# bristol_longshot.net
KiCad netlist of a schematic drawn in EAGLE
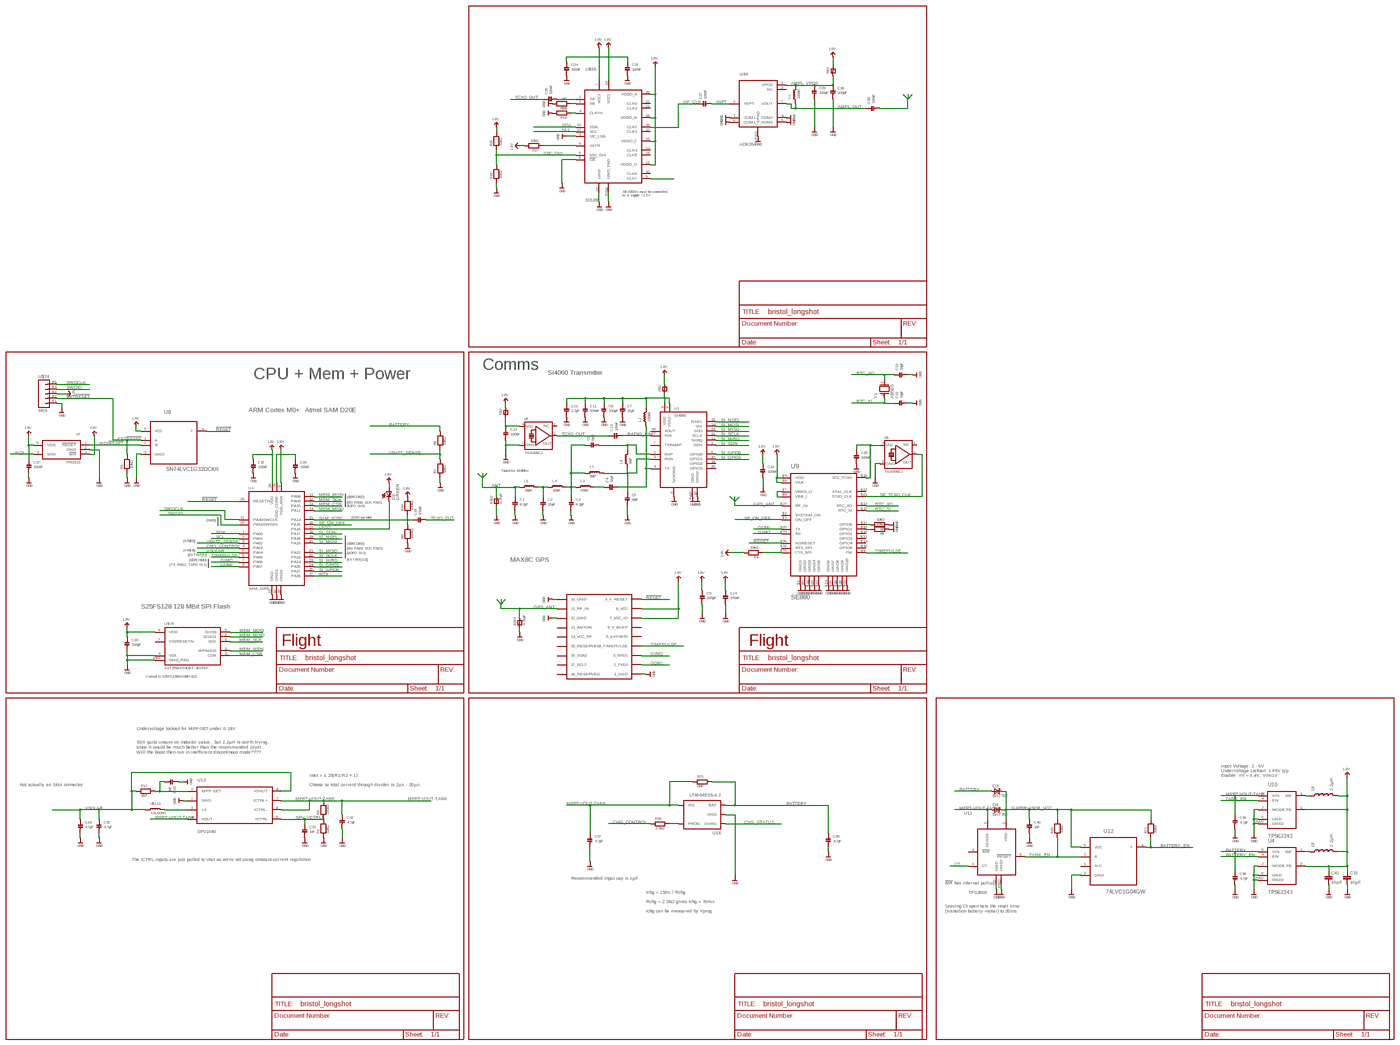
[diagram p0: schematic, sheet 1, overview]
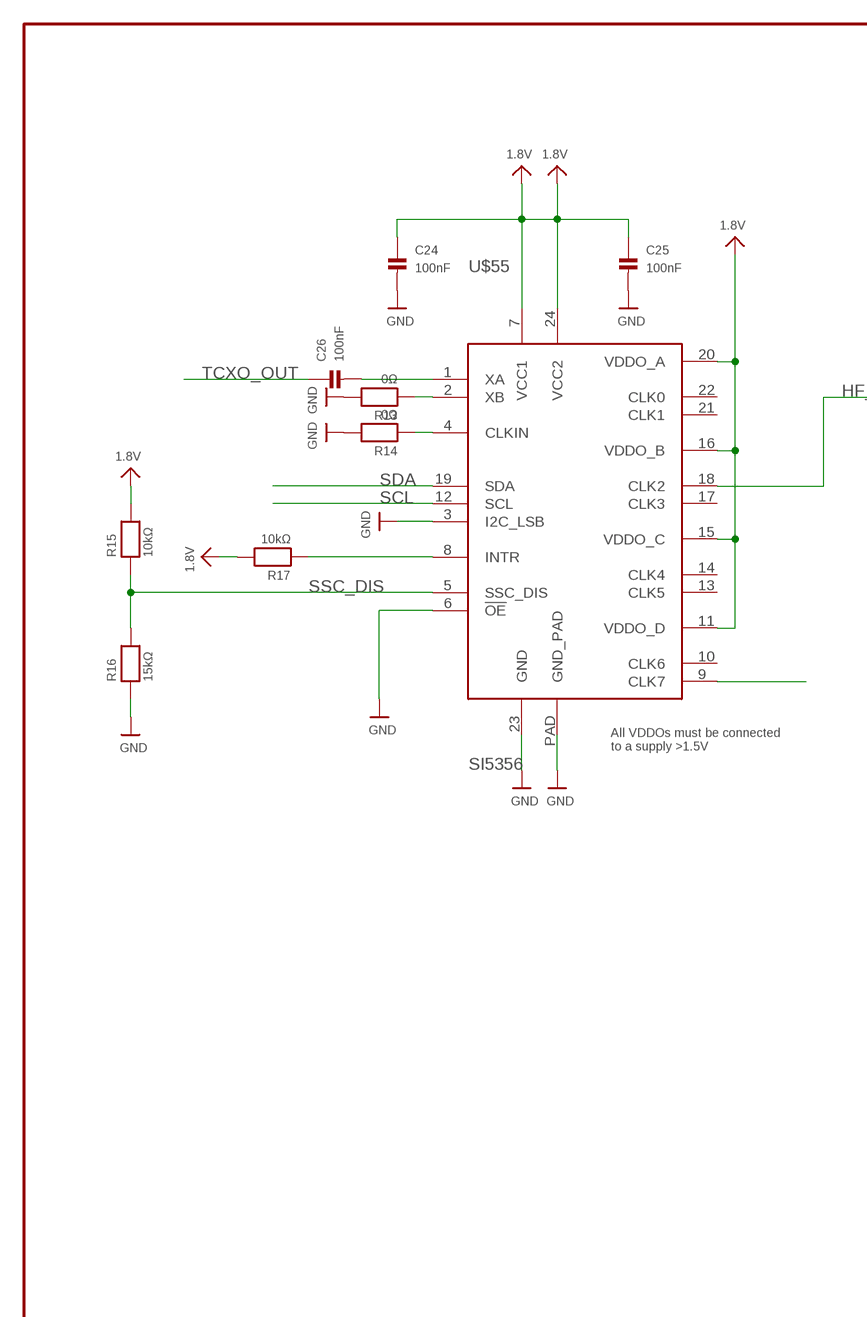
[diagram p1: schematic, sheet 1, part 1 of 4]
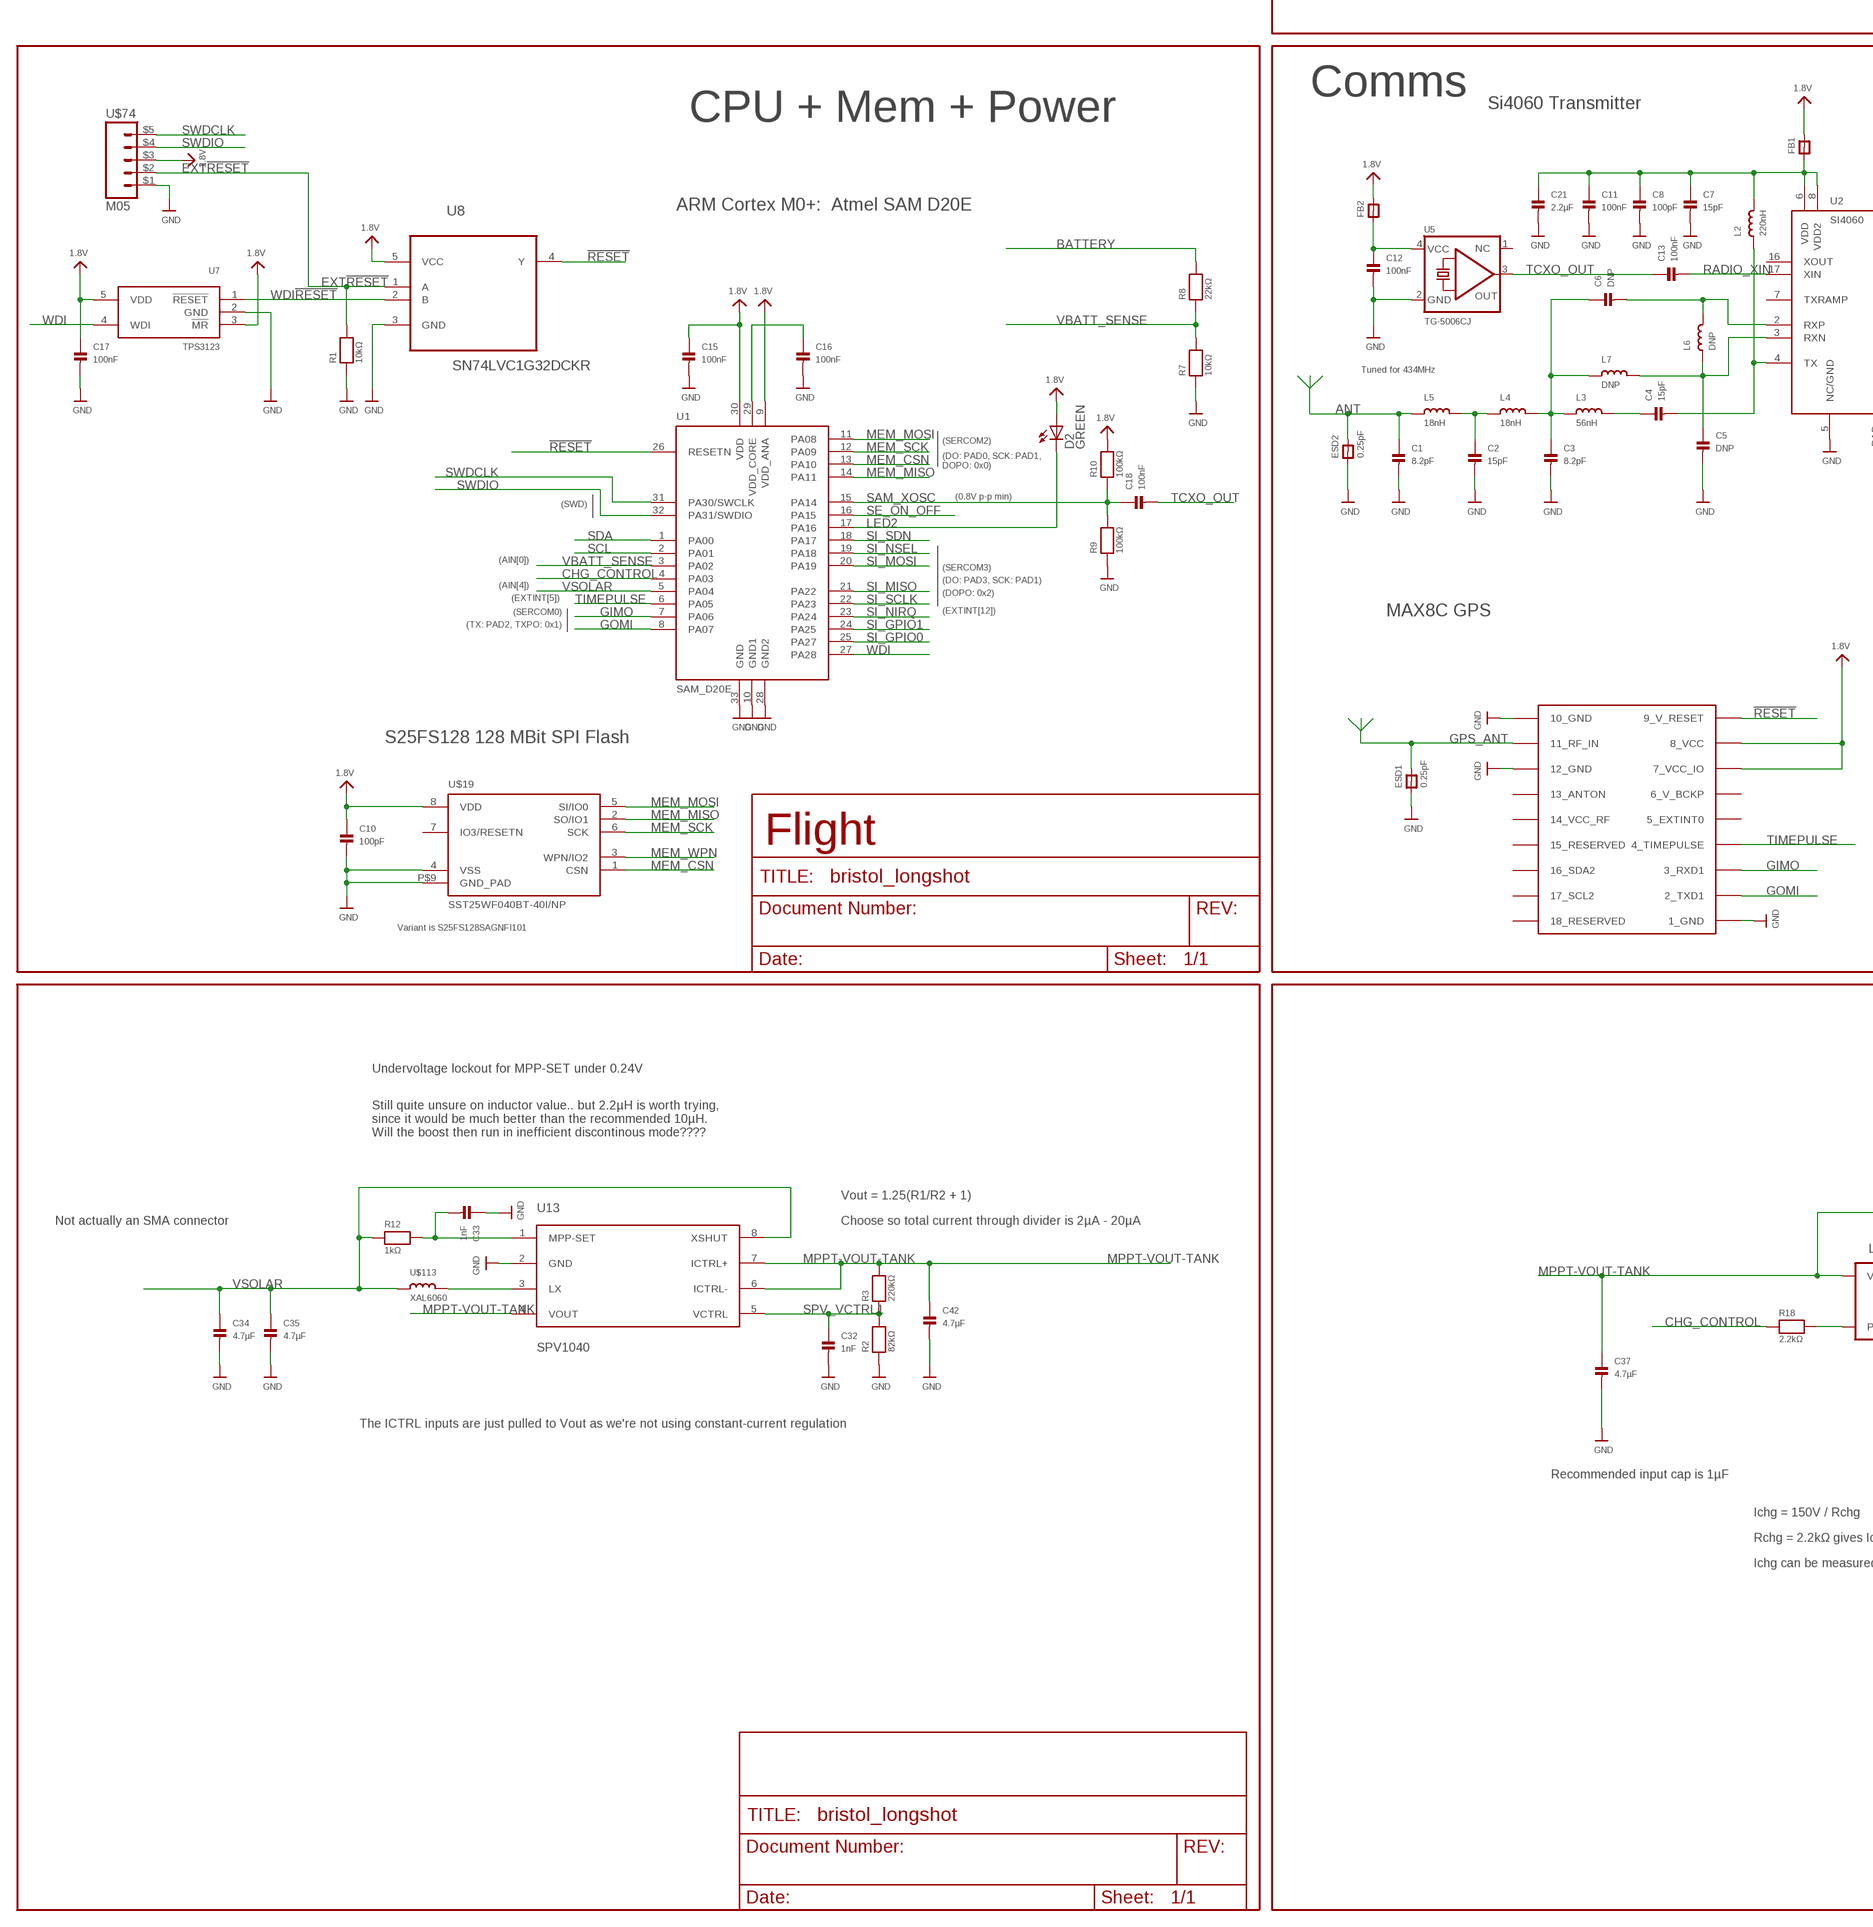
[diagram p2: schematic, sheet 1, part 2 of 4]
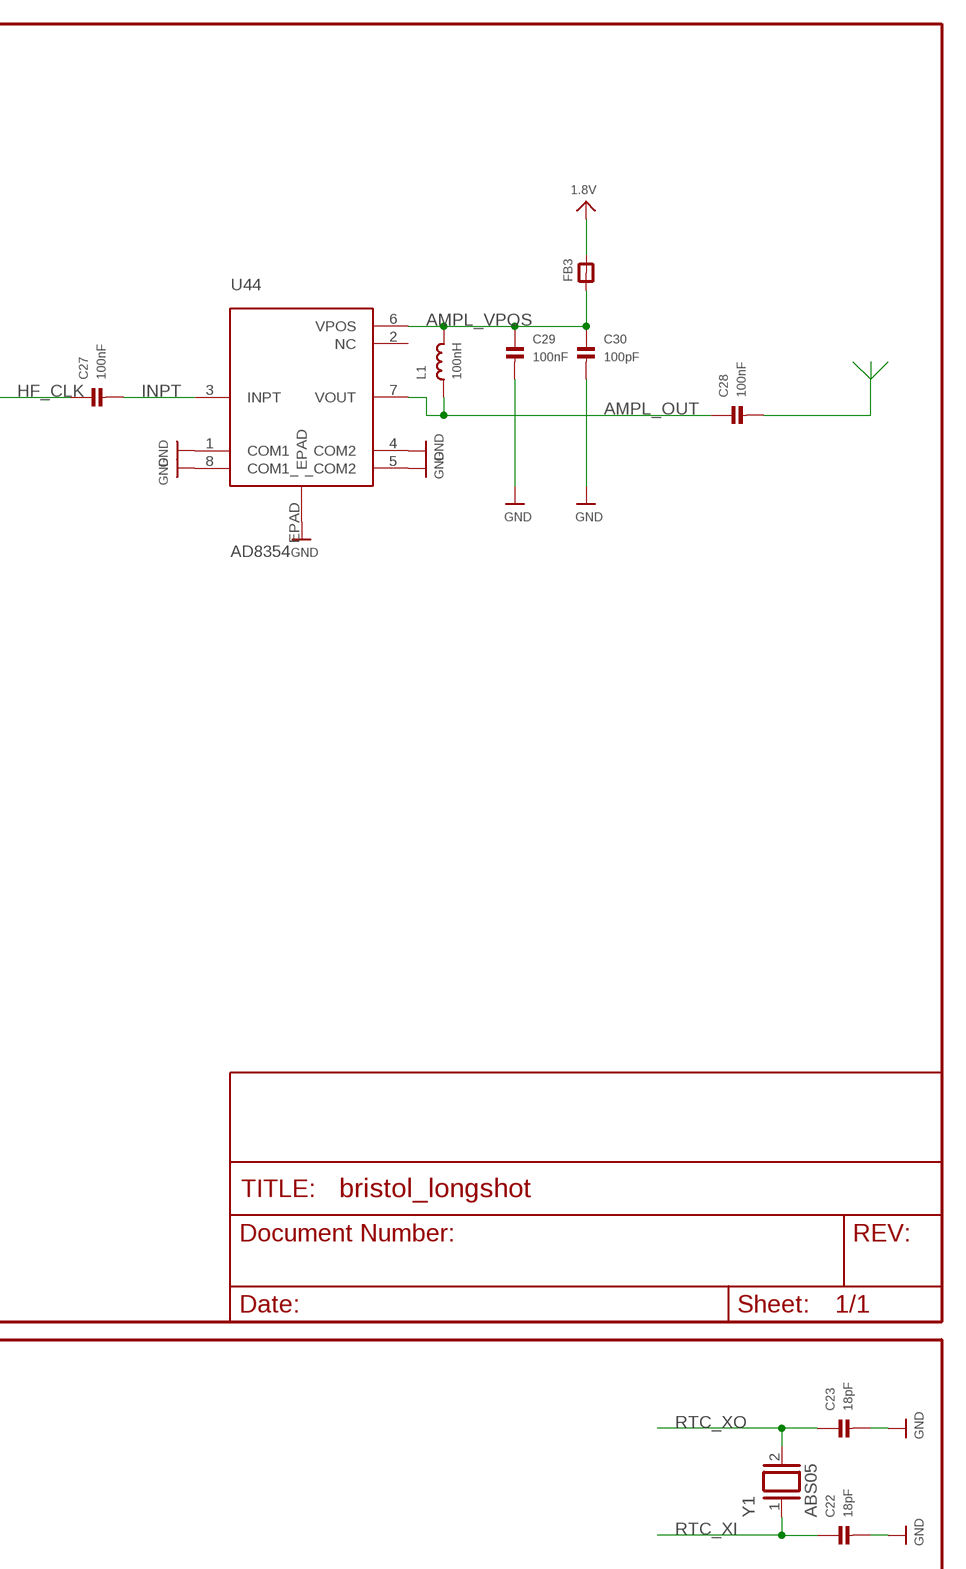
[diagram p3: schematic, sheet 1, part 3 of 4]
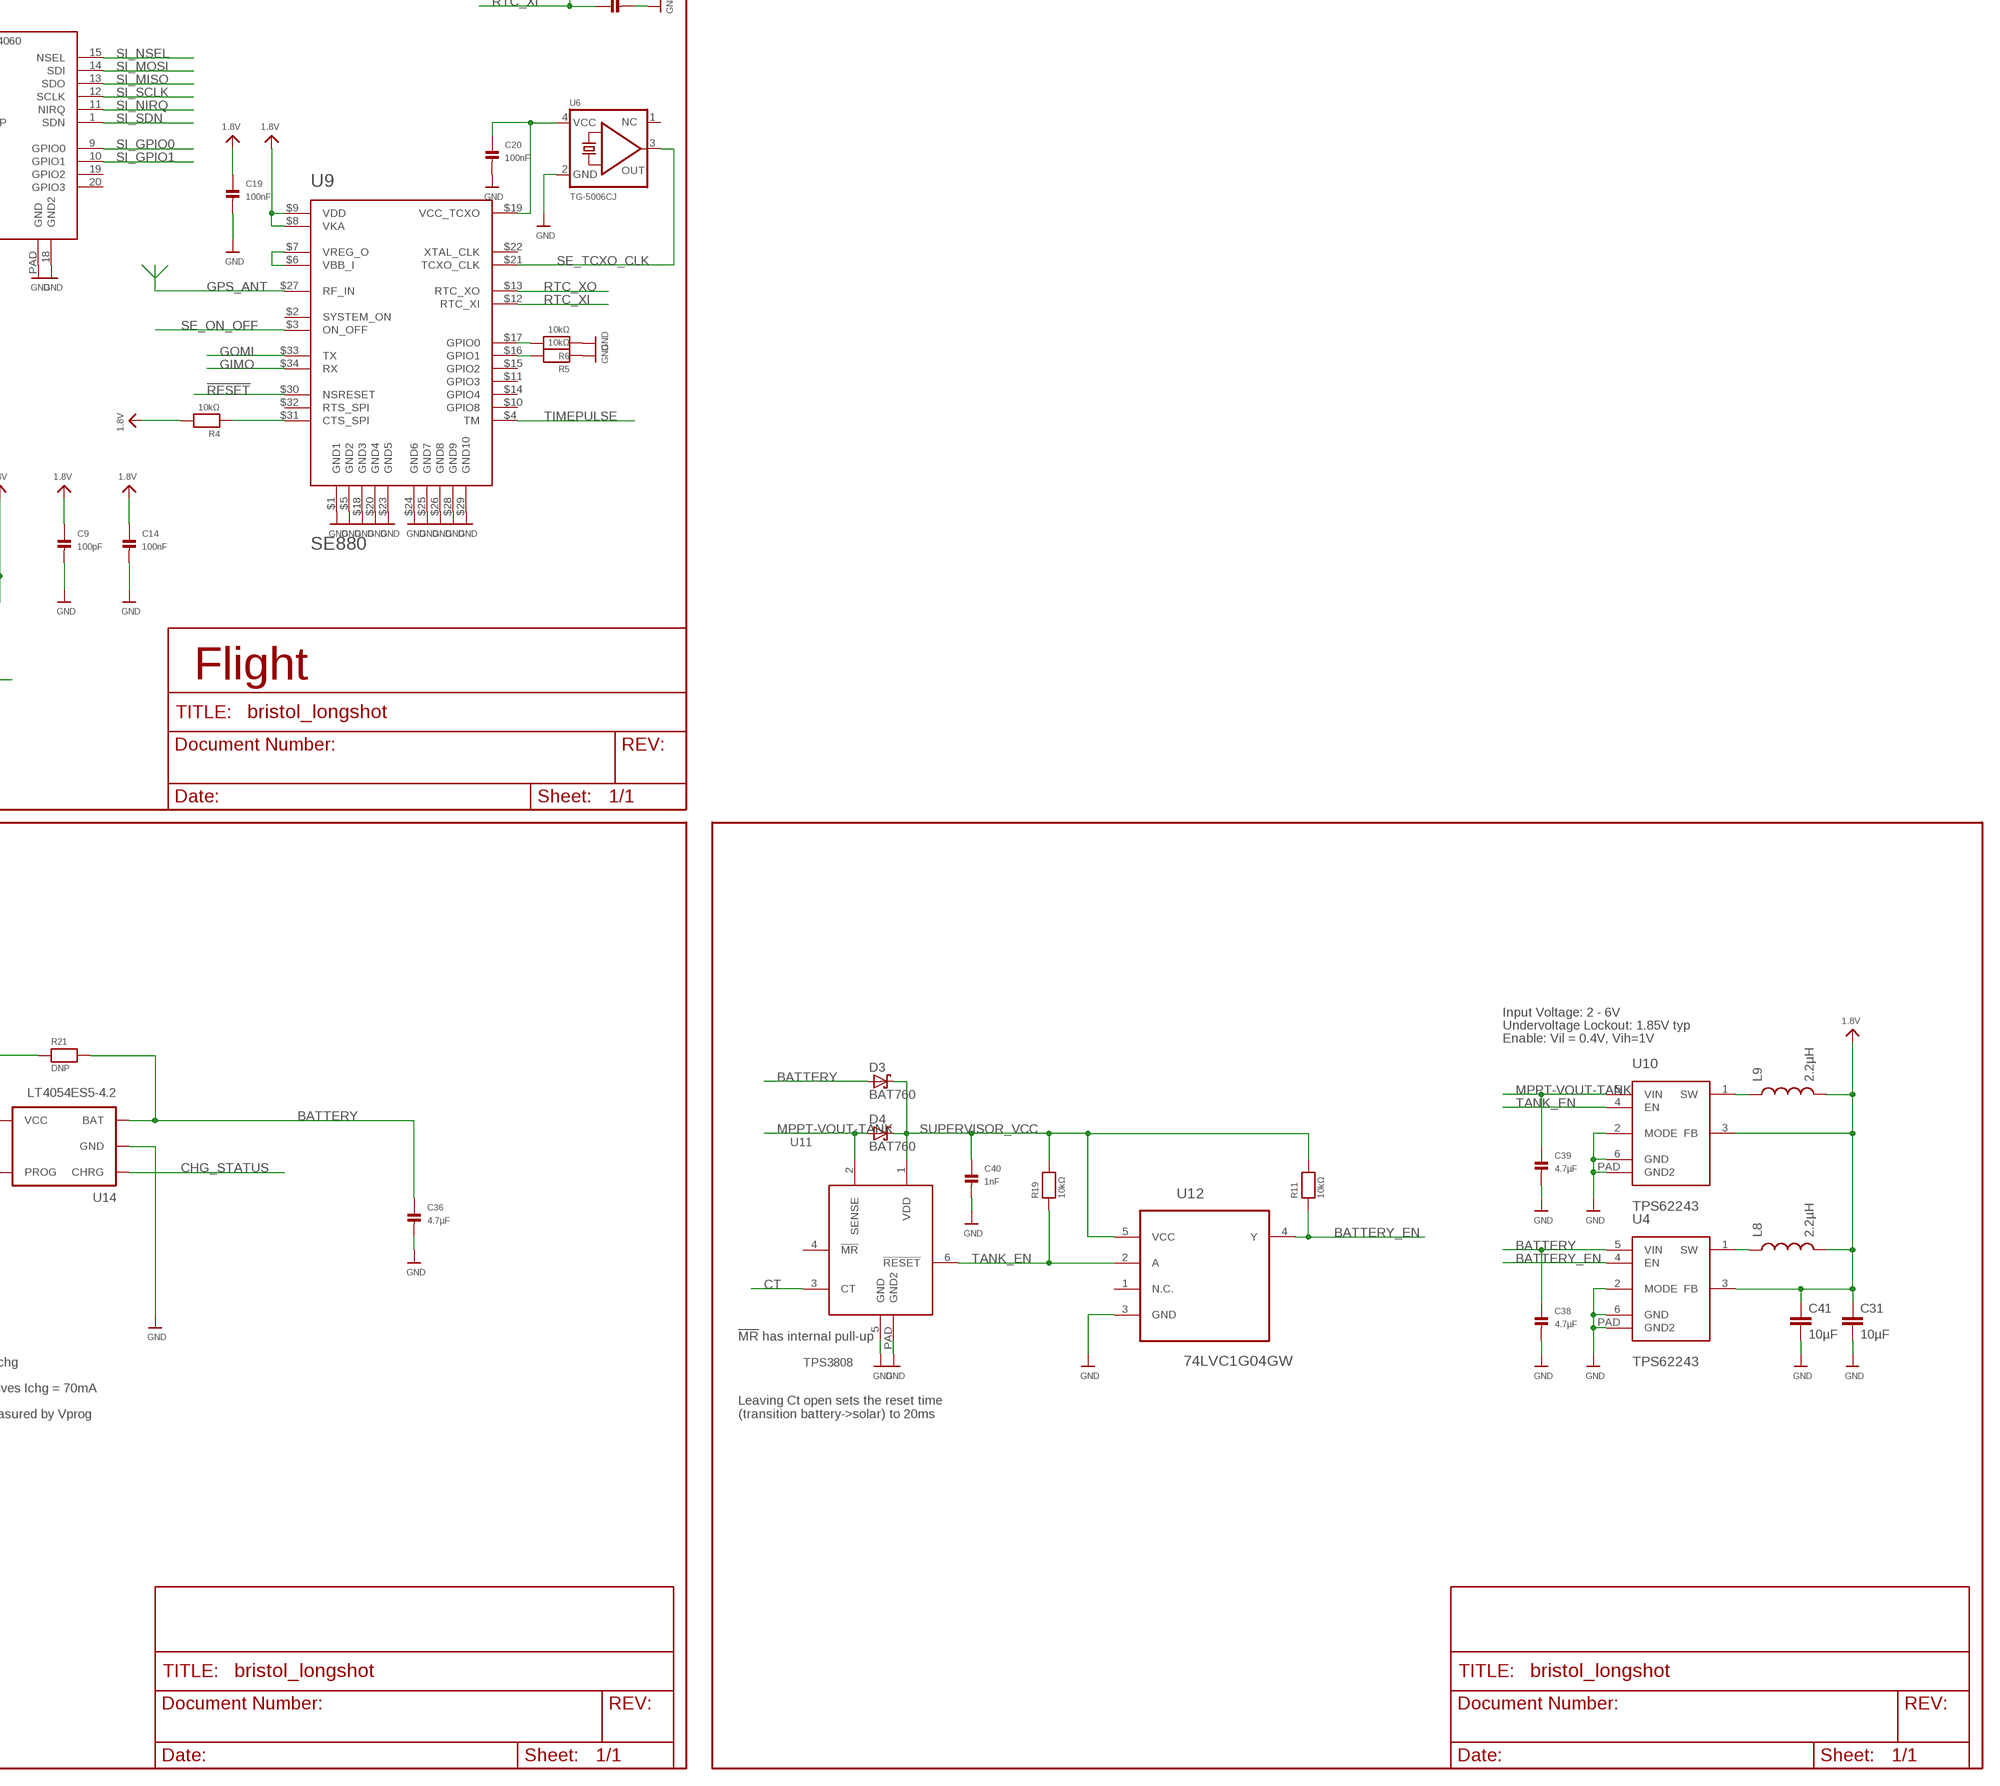
[diagram p4: schematic, sheet 1, part 4 of 4]

(export (version "E")
  (design (tool "Eeschema 10.0.6"))
  (components
    (comp (ref "C1")
      (value "8.2pF")
      (footprint "eagle-import:_0402")
      (libsource (lib "eagle-import") (part "CAP_CERAMIC_0402"))
    )
    (comp (ref "C2")
      (value "15pF")
      (footprint "eagle-import:_0402")
      (libsource (lib "eagle-import") (part "CAP_CERAMIC_0402"))
    )
    (comp (ref "C3")
      (value "8.2pF")
      (footprint "eagle-import:_0402")
      (libsource (lib "eagle-import") (part "CAP_CERAMIC_0402"))
    )
    (comp (ref "C4")
      (value "15pF")
      (footprint "eagle-import:_0402")
      (libsource (lib "eagle-import") (part "CAP_CERAMIC_0402"))
    )
    (comp (ref "C5")
      (value "DNP")
      (footprint "eagle-import:_0402")
      (libsource (lib "eagle-import") (part "CAP_CERAMIC_0402"))
    )
    (comp (ref "C6")
      (value "DNP")
      (footprint "eagle-import:_0402")
      (libsource (lib "eagle-import") (part "CAP_CERAMIC_0402"))
    )
    (comp (ref "C7")
      (value "15pF")
      (footprint "eagle-import:_0402")
      (libsource (lib "eagle-import") (part "CAP_CERAMIC_0402"))
    )
    (comp (ref "C8")
      (value "100pF")
      (footprint "eagle-import:_0402")
      (libsource (lib "eagle-import") (part "CAP_CERAMIC_0402"))
    )
    (comp (ref "C9")
      (value "100pF")
      (footprint "eagle-import:_0402")
      (libsource (lib "eagle-import") (part "CAP_CERAMIC_0402"))
    )
    (comp (ref "C10")
      (value "100pF")
      (footprint "eagle-import:_0402")
      (libsource (lib "eagle-import") (part "CAP_CERAMIC_0402"))
    )
    (comp (ref "C11")
      (value "100nF")
      (footprint "eagle-import:_0402")
      (libsource (lib "eagle-import") (part "CAP_CERAMIC_0402"))
    )
    (comp (ref "C12")
      (value "100nF")
      (footprint "eagle-import:_0402")
      (libsource (lib "eagle-import") (part "CAP_CERAMIC_0402"))
    )
    (comp (ref "C13")
      (value "100nF")
      (footprint "eagle-import:_0402")
      (libsource (lib "eagle-import") (part "CAP_CERAMIC_0402"))
    )
    (comp (ref "C14")
      (value "100nF")
      (footprint "eagle-import:_0402")
      (libsource (lib "eagle-import") (part "CAP_CERAMIC_0402"))
    )
    (comp (ref "C15")
      (value "100nF")
      (footprint "eagle-import:_0402")
      (libsource (lib "eagle-import") (part "CAP_CERAMIC_0402"))
    )
    (comp (ref "C16")
      (value "100nF")
      (footprint "eagle-import:_0402")
      (libsource (lib "eagle-import") (part "CAP_CERAMIC_0402"))
    )
    (comp (ref "C17")
      (value "100nF")
      (footprint "eagle-import:_0402")
      (libsource (lib "eagle-import") (part "CAP_CERAMIC_0402"))
    )
    (comp (ref "C18")
      (value "100nF")
      (footprint "eagle-import:_0402")
      (libsource (lib "eagle-import") (part "CAP_CERAMIC_0402"))
    )
    (comp (ref "C19")
      (value "100nF")
      (footprint "eagle-import:_0402")
      (libsource (lib "eagle-import") (part "CAP_CERAMIC_0402"))
    )
    (comp (ref "C20")
      (value "100nF")
      (footprint "eagle-import:_0402")
      (libsource (lib "eagle-import") (part "CAP_CERAMIC_0402"))
    )
    (comp (ref "C21")
      (value "2.2µF")
      (footprint "eagle-import:_0402")
      (libsource (lib "eagle-import") (part "CAP_CERAMIC_0402"))
    )
    (comp (ref "C22")
      (value "18pF")
      (footprint "eagle-import:_0402")
      (libsource (lib "eagle-import") (part "CAP_CERAMIC_0402"))
    )
    (comp (ref "C23")
      (value "18pF")
      (footprint "eagle-import:_0402")
      (libsource (lib "eagle-import") (part "CAP_CERAMIC_0402"))
    )
    (comp (ref "C24")
      (value "100nF")
      (footprint "eagle-import:_0402")
      (libsource (lib "eagle-import") (part "CAP_CERAMIC_0402"))
    )
    (comp (ref "C25")
      (value "100nF")
      (footprint "eagle-import:_0402")
      (libsource (lib "eagle-import") (part "CAP_CERAMIC_0402"))
    )
    (comp (ref "C26")
      (value "100nF")
      (footprint "eagle-import:_0402")
      (libsource (lib "eagle-import") (part "CAP_CERAMIC_0402"))
    )
    (comp (ref "C27")
      (value "100nF")
      (footprint "eagle-import:_0402")
      (libsource (lib "eagle-import") (part "CAP_CERAMIC_0402"))
    )
    (comp (ref "C28")
      (value "100nF")
      (footprint "eagle-import:_0402")
      (libsource (lib "eagle-import") (part "CAP_CERAMIC_0402"))
    )
    (comp (ref "C29")
      (value "100nF")
      (footprint "eagle-import:_0402")
      (libsource (lib "eagle-import") (part "CAP_CERAMIC_0402"))
    )
    (comp (ref "C30")
      (value "100pF")
      (footprint "eagle-import:_0402")
      (libsource (lib "eagle-import") (part "CAP_CERAMIC_0402"))
    )
    (comp (ref "C31")
      (value "10µF")
      (footprint "eagle-import:C0603K")
      (libsource (lib "eagle-import") (part "C-EUC0603K"))
    )
    (comp (ref "C32")
      (value "1nF")
      (footprint "eagle-import:_0402")
      (libsource (lib "eagle-import") (part "CAP_CERAMIC_0402"))
    )
    (comp (ref "C33")
      (value "1nF")
      (footprint "eagle-import:_0402")
      (libsource (lib "eagle-import") (part "CAP_CERAMIC_0402"))
    )
    (comp (ref "C34")
      (value "4.7µF")
      (footprint "eagle-import:_0402")
      (libsource (lib "eagle-import") (part "CAP_CERAMIC_0402"))
    )
    (comp (ref "C35")
      (value "4.7µF")
      (footprint "eagle-import:_0402")
      (libsource (lib "eagle-import") (part "CAP_CERAMIC_0402"))
    )
    (comp (ref "C36")
      (value "4.7µF")
      (footprint "eagle-import:_0402")
      (libsource (lib "eagle-import") (part "CAP_CERAMIC_0402"))
    )
    (comp (ref "C37")
      (value "4.7µF")
      (footprint "eagle-import:_0402")
      (libsource (lib "eagle-import") (part "CAP_CERAMIC_0402"))
    )
    (comp (ref "C38")
      (value "4.7µF")
      (footprint "eagle-import:_0402")
      (libsource (lib "eagle-import") (part "CAP_CERAMIC_0402"))
    )
    (comp (ref "C39")
      (value "4.7µF")
      (footprint "eagle-import:_0402")
      (libsource (lib "eagle-import") (part "CAP_CERAMIC_0402"))
    )
    (comp (ref "C40")
      (value "1nF")
      (footprint "eagle-import:_0402")
      (libsource (lib "eagle-import") (part "CAP_CERAMIC_0402"))
    )
    (comp (ref "C41")
      (value "10µF")
      (footprint "eagle-import:C0603K")
      (libsource (lib "eagle-import") (part "C-EUC0603K"))
    )
    (comp (ref "C42")
      (value "4.7µF")
      (footprint "eagle-import:_0402")
      (libsource (lib "eagle-import") (part "CAP_CERAMIC_0402"))
    )
    (comp (ref "D2")
      (value "GREEN")
      (footprint "eagle-import:CHIPLED_0603")
      (libsource (lib "eagle-import") (part "LEDCHIPLED_0603"))
    )
    (comp (ref "D3")
      (value "BAT760")
      (footprint "eagle-import:SOD323")
      (libsource (lib "eagle-import") (part "BAT760"))
    )
    (comp (ref "D4")
      (value "BAT760")
      (footprint "eagle-import:SOD323")
      (libsource (lib "eagle-import") (part "BAT760"))
    )
    (comp (ref "ESD1")
      (value "0.25pF")
      (footprint "eagle-import:_0603MP")
      (libsource (lib "eagle-import") (part "FERRITE_0603MP"))
    )
    (comp (ref "ESD2")
      (value "0.25pF")
      (footprint "eagle-import:_0603MP")
      (libsource (lib "eagle-import") (part "FERRITE_0603MP"))
    )
    (comp (ref "FB1")
      (value "FERRITE_0402")
      (footprint "eagle-import:_0402")
      (libsource (lib "eagle-import") (part "FERRITE_0402"))
    )
    (comp (ref "FB2")
      (value "FERRITE_0402")
      (footprint "eagle-import:_0402")
      (libsource (lib "eagle-import") (part "FERRITE_0402"))
    )
    (comp (ref "FB3")
      (value "FERRITE_0402")
      (footprint "eagle-import:_0402")
      (libsource (lib "eagle-import") (part "FERRITE_0402"))
    )
    (comp (ref "L1")
      (value "100nH")
      (footprint "eagle-import:_0402")
      (libsource (lib "eagle-import") (part "INDUCTOR_0402"))
    )
    (comp (ref "L2")
      (value "220nH")
      (footprint "eagle-import:_0402")
      (libsource (lib "eagle-import") (part "INDUCTOR_0402"))
    )
    (comp (ref "L3")
      (value "56nH")
      (footprint "eagle-import:_0402")
      (libsource (lib "eagle-import") (part "INDUCTOR_0402"))
    )
    (comp (ref "L4")
      (value "18nH")
      (footprint "eagle-import:_0402")
      (libsource (lib "eagle-import") (part "INDUCTOR_0402"))
    )
    (comp (ref "L5")
      (value "18nH")
      (footprint "eagle-import:_0402")
      (libsource (lib "eagle-import") (part "INDUCTOR_0402"))
    )
    (comp (ref "L6")
      (value "DNP")
      (footprint "eagle-import:_0402")
      (libsource (lib "eagle-import") (part "INDUCTOR_0402"))
    )
    (comp (ref "L7")
      (value "DNP")
      (footprint "eagle-import:_0402")
      (libsource (lib "eagle-import") (part "INDUCTOR_0402"))
    )
    (comp (ref "L8")
      (value "2.2µH")
      (footprint "eagle-import:1007")
      (libsource (lib "eagle-import") (part "INDUCTOR1007"))
    )
    (comp (ref "L9")
      (value "2.2µH")
      (footprint "eagle-import:1007")
      (libsource (lib "eagle-import") (part "INDUCTOR1007"))
    )
    (comp (ref "R1")
      (value "10kΩ")
      (footprint "eagle-import:_0402")
      (libsource (lib "eagle-import") (part "RESISTOR_0402"))
    )
    (comp (ref "R2")
      (value "82kΩ")
      (footprint "eagle-import:_0402")
      (libsource (lib "eagle-import") (part "RESISTOR_0402"))
    )
    (comp (ref "R3")
      (value "220kΩ")
      (footprint "eagle-import:_0402")
      (libsource (lib "eagle-import") (part "RESISTOR_0402"))
    )
    (comp (ref "R4")
      (value "10kΩ")
      (footprint "eagle-import:_0402")
      (libsource (lib "eagle-import") (part "RESISTOR_0402"))
    )
    (comp (ref "R5")
      (value "10kΩ")
      (footprint "eagle-import:_0402")
      (libsource (lib "eagle-import") (part "RESISTOR_0402"))
    )
    (comp (ref "R6")
      (value "10kΩ")
      (footprint "eagle-import:_0402")
      (libsource (lib "eagle-import") (part "RESISTOR_0402"))
    )
    (comp (ref "R7")
      (value "10kΩ")
      (footprint "eagle-import:_0402")
      (libsource (lib "eagle-import") (part "RESISTOR_0402"))
    )
    (comp (ref "R8")
      (value "22kΩ")
      (footprint "eagle-import:_0402")
      (libsource (lib "eagle-import") (part "RESISTOR_0402"))
    )
    (comp (ref "R9")
      (value "100kΩ")
      (footprint "eagle-import:_0402")
      (libsource (lib "eagle-import") (part "RESISTOR_0402"))
    )
    (comp (ref "R10")
      (value "100kΩ")
      (footprint "eagle-import:_0402")
      (libsource (lib "eagle-import") (part "RESISTOR_0402"))
    )
    (comp (ref "R11")
      (value "10kΩ")
      (footprint "eagle-import:_0402")
      (libsource (lib "eagle-import") (part "RESISTOR_0402"))
    )
    (comp (ref "R12")
      (value "1kΩ")
      (footprint "eagle-import:_0402")
      (libsource (lib "eagle-import") (part "RESISTOR_0402"))
    )
    (comp (ref "R13")
      (value "0Ω")
      (footprint "eagle-import:_0402")
      (libsource (lib "eagle-import") (part "RESISTOR_0402"))
    )
    (comp (ref "R14")
      (value "0Ω")
      (footprint "eagle-import:_0402")
      (libsource (lib "eagle-import") (part "RESISTOR_0402"))
    )
    (comp (ref "R15")
      (value "10kΩ")
      (footprint "eagle-import:_0402")
      (libsource (lib "eagle-import") (part "RESISTOR_0402"))
    )
    (comp (ref "R16")
      (value "15kΩ")
      (footprint "eagle-import:_0402")
      (libsource (lib "eagle-import") (part "RESISTOR_0402"))
    )
    (comp (ref "R17")
      (value "10kΩ")
      (footprint "eagle-import:_0402")
      (libsource (lib "eagle-import") (part "RESISTOR_0402"))
    )
    (comp (ref "R18")
      (value "2.2kΩ")
      (footprint "eagle-import:_0402")
      (libsource (lib "eagle-import") (part "RESISTOR_0402"))
    )
    (comp (ref "R19")
      (value "10kΩ")
      (footprint "eagle-import:_0402")
      (libsource (lib "eagle-import") (part "RESISTOR_0402"))
    )
    (comp (ref "R21")
      (value "DNP")
      (footprint "eagle-import:_0402")
      (libsource (lib "eagle-import") (part "RESISTOR_0402"))
    )
    (comp (ref "U$19")
      (value "SST25WF040BT-40I/NP")
      (footprint "eagle-import:USON-8")
      (libsource (lib "eagle-import") (part "SST25WF040BT-40I/NP"))
    )
    (comp (ref "U$55")
      (value "SI5356")
      (footprint "eagle-import:QFN24_4MM")
      (libsource (lib "eagle-import") (part "SI5356"))
    )
    (comp (ref "U$74")
      (value "M05")
      (footprint "eagle-import:M05_SIDE")
      (libsource (lib "eagle-import") (part "M05"))
    )
    (comp (ref "U$113")
      (value "XAL6060")
      (footprint "eagle-import:XAL60")
      (libsource (lib "eagle-import") (part "XAL6060"))
    )
    (comp (ref "U1")
      (value "SAM_D20E")
      (footprint "eagle-import:QFN32_5MM")
      (libsource (lib "eagle-import") (part "SAM_D20E"))
    )
    (comp (ref "U2")
      (value "SI4060")
      (footprint "eagle-import:QFN20")
      (libsource (lib "eagle-import") (part "SI4060"))
    )
    (comp (ref "U3")
      (value "UBLOX_MAX")
      (footprint "eagle-import:UBLOX_MAX")
      (libsource (lib "eagle-import") (part "UBLOX_MAX"))
    )
    (comp (ref "U4")
      (value "TPS62243")
      (footprint "eagle-import:S-PWSON-N6")
      (libsource (lib "eagle-import") (part "TPS62243"))
    )
    (comp (ref "U5")
      (value "TG-5006CJ")
      (footprint "eagle-import:TC-5006CJ")
      (libsource (lib "eagle-import") (part "TG-5006CJ"))
    )
    (comp (ref "U6")
      (value "TG-5006CJ")
      (footprint "eagle-import:TC-5006CJ")
      (libsource (lib "eagle-import") (part "TG-5006CJ"))
    )
    (comp (ref "U7")
      (value "TPS3123")
      (footprint "eagle-import:SOT23-5")
      (libsource (lib "eagle-import") (part "TPS3123"))
    )
    (comp (ref "U8")
      (value "SN74LVC1G32DCKR")
      (footprint "eagle-import:SOT65P210X110-5N")
      (libsource (lib "eagle-import") (part "SN74LVC1G32DCKR"))
    )
    (comp (ref "U9")
      (value "SE880")
      (footprint "eagle-import:SE880")
      (libsource (lib "eagle-import") (part "SE880"))
    )
    (comp (ref "U10")
      (value "TPS62243")
      (footprint "eagle-import:S-PWSON-N6")
      (libsource (lib "eagle-import") (part "TPS62243"))
    )
    (comp (ref "U11")
      (value "TPS3808")
      (footprint "eagle-import:S-PWSON-N6")
      (libsource (lib "eagle-import") (part "TPS3808"))
    )
    (comp (ref "U12")
      (value "74LVC1G04GW")
      (footprint "eagle-import:SOT65P210X110-5N")
      (libsource (lib "eagle-import") (part "74LVC1G04GW"))
    )
    (comp (ref "U13")
      (value "SPV1040")
      (footprint "eagle-import:TSSOP8")
      (libsource (lib "eagle-import") (part "SPV1040"))
    )
    (comp (ref "U14")
      (value "LT4054ES5-4.2")
      (footprint "eagle-import:SOT23-5")
      (libsource (lib "eagle-import") (part "LT4054ES5-4.2"))
    )
    (comp (ref "U44")
      (value "AD8354")
      (footprint "eagle-import:LFCSP_VD_8")
      (libsource (lib "eagle-import") (part "AD8354"))
    )
    (comp (ref "Y1")
      (value "ABS05")
      (footprint "eagle-import:ABS05")
      (libsource (lib "eagle-import") (part "ABS05"))
    )
  )
  (nets
    (net (code "1") (name "/AMPL_OUT") (class "Default")
      (node (ref "C28") (pin "1") (pinfunction "P$1_1") (pintype "passive"))
      (node (ref "L1") (pin "1") (pinfunction "1_1") (pintype "passive"))
      (node (ref "U44") (pin "7") (pinfunction "VOUT_7") (pintype "bidirectional"))
    )
    (net (code "2") (name "/AMPL_VPOS") (class "Default")
      (node (ref "C29") (pin "1") (pinfunction "P$1_1") (pintype "passive"))
      (node (ref "C30") (pin "1") (pinfunction "P$1_1") (pintype "passive"))
      (node (ref "FB3") (pin "1") (pinfunction "P$1_1") (pintype "passive"))
      (node (ref "L1") (pin "2") (pinfunction "2_2") (pintype "passive"))
      (node (ref "U44") (pin "6") (pinfunction "VPOS_6") (pintype "bidirectional"))
    )
    (net (code "3") (name "/ANT") (class "Default")
      (node (ref "C1") (pin "1") (pinfunction "P$1_1") (pintype "passive"))
      (node (ref "ESD2") (pin "2") (pinfunction "P$2_2") (pintype "passive"))
      (node (ref "L5") (pin "1") (pinfunction "1_1") (pintype "passive"))
    )
    (net (code "4") (name "/BATTERY") (class "Default")
      (node (ref "C36") (pin "1") (pinfunction "P$1_1") (pintype "passive"))
      (node (ref "C38") (pin "1") (pinfunction "P$1_1") (pintype "passive"))
      (node (ref "D3") (pin "A") (pinfunction "A_A") (pintype "passive"))
      (node (ref "R21") (pin "2") (pinfunction "2_2") (pintype "passive"))
      (node (ref "R8") (pin "2") (pinfunction "2_2") (pintype "passive"))
      (node (ref "U14") (pin "3") (pinfunction "BAT_3") (pintype "input"))
      (node (ref "U4") (pin "5") (pinfunction "VIN_5") (pintype "bidirectional"))
    )
    (net (code "5") (name "/BATTERY_EN") (class "Default")
      (node (ref "R11") (pin "1") (pinfunction "1_1") (pintype "passive"))
      (node (ref "U12") (pin "4") (pinfunction "Y_4") (pintype "output"))
      (node (ref "U4") (pin "4") (pinfunction "EN_4") (pintype "bidirectional"))
    )
    (net (code "6") (name "/CHG_CONTROL") (class "Default")
      (node (ref "R18") (pin "1") (pinfunction "1_1") (pintype "passive"))
      (node (ref "U1") (pin "4") (pinfunction "PA03_4") (pintype "bidirectional"))
    )
    (net (code "7") (name "/CHG_STATUS") (class "Default")
      (node (ref "U14") (pin "1") (pinfunction "CHRG_1") (pintype "input"))
    )
    (net (code "8") (name "/CT") (class "Default")
      (node (ref "U11") (pin "3") (pinfunction "CT_3") (pintype "bidirectional"))
    )
    (net (code "9") (name "/EXT~{RESET}") (class "Default")
      (node (ref "R1") (pin "2") (pinfunction "2_2") (pintype "passive"))
      (node (ref "U$74") (pin "$2") (pinfunction "2_$2") (pintype "passive"))
      (node (ref "U8") (pin "1") (pinfunction "A_1") (pintype "input"))
    )
    (net (code "10") (name "/GIMO") (class "Default")
      (node (ref "U1") (pin "7") (pinfunction "PA06_7") (pintype "bidirectional"))
      (node (ref "U3") (pin "3_RXD1") (pinfunction "3_RXD1_3_RXD1") (pintype "bidirectional"))
      (node (ref "U9") (pin "$34") (pinfunction "RX_$34") (pintype "bidirectional"))
    )
    (net (code "11") (name "/GOMI") (class "Default")
      (node (ref "U1") (pin "8") (pinfunction "PA07_8") (pintype "bidirectional"))
      (node (ref "U3") (pin "2_TXD1") (pinfunction "2_TXD1_2_TXD1") (pintype "bidirectional"))
      (node (ref "U9") (pin "$33") (pinfunction "TX_$33") (pintype "bidirectional"))
    )
    (net (code "12") (name "/GPS_ANT") (class "Default")
      (node (ref "ESD1") (pin "2") (pinfunction "P$2_2") (pintype "passive"))
      (node (ref "U3") (pin "11_RF_IN") (pinfunction "11_RF_IN_11_RF_IN") (pintype "bidirectional"))
      (node (ref "U9") (pin "$27") (pinfunction "RF_IN_$27") (pintype "bidirectional"))
    )
    (net (code "13") (name "/HF_CLK") (class "Default")
      (node (ref "C27") (pin "1") (pinfunction "P$1_1") (pintype "passive"))
      (node (ref "U$55") (pin "18") (pinfunction "CLK2_18") (pintype "bidirectional"))
    )
    (net (code "14") (name "/INPT") (class "Default")
      (node (ref "C27") (pin "2") (pinfunction "P$2_2") (pintype "passive"))
      (node (ref "U44") (pin "3") (pinfunction "INPT_3") (pintype "bidirectional"))
    )
    (net (code "15") (name "/LED2") (class "Default")
      (node (ref "D2") (pin "C") (pinfunction "C_C") (pintype "passive"))
      (node (ref "U1") (pin "17") (pinfunction "PA16_17") (pintype "bidirectional"))
    )
    (net (code "16") (name "/MEM_CSN") (class "Default")
      (node (ref "U$19") (pin "1") (pinfunction "CSN_1") (pintype "input"))
      (node (ref "U1") (pin "13") (pinfunction "PA10_13") (pintype "bidirectional"))
    )
    (net (code "17") (name "/MEM_MISO") (class "Default")
      (node (ref "U$19") (pin "2") (pinfunction "SO/IO1_2") (pintype "output"))
      (node (ref "U1") (pin "14") (pinfunction "PA11_14") (pintype "bidirectional"))
    )
    (net (code "18") (name "/MEM_MOSI") (class "Default")
      (node (ref "U$19") (pin "5") (pinfunction "SI/IO0_5") (pintype "bidirectional"))
      (node (ref "U1") (pin "11") (pinfunction "PA08_11") (pintype "bidirectional"))
    )
    (net (code "19") (name "/MEM_SCK") (class "Default")
      (node (ref "U$19") (pin "6") (pinfunction "SCK_6") (pintype "input"))
      (node (ref "U1") (pin "12") (pinfunction "PA09_12") (pintype "bidirectional"))
    )
    (net (code "20") (name "/MEM_WPN") (class "Default")
      (node (ref "U$19") (pin "3") (pinfunction "WPN/IO2_3") (pintype "output"))
    )
    (net (code "21") (name "/MPPT-VOUT-TANK") (class "Default")
      (node (ref "C37") (pin "1") (pinfunction "P$1_1") (pintype "passive"))
      (node (ref "C39") (pin "1") (pinfunction "P$1_1") (pintype "passive"))
      (node (ref "C42") (pin "1") (pinfunction "P$1_1") (pintype "passive"))
      (node (ref "D4") (pin "A") (pinfunction "A_A") (pintype "passive"))
      (node (ref "R21") (pin "1") (pinfunction "1_1") (pintype "passive"))
      (node (ref "R3") (pin "2") (pinfunction "2_2") (pintype "passive"))
      (node (ref "U10") (pin "5") (pinfunction "VIN_5") (pintype "bidirectional"))
      (node (ref "U11") (pin "2") (pinfunction "SENSE_2") (pintype "bidirectional"))
      (node (ref "U13") (pin "4") (pinfunction "VOUT_4") (pintype "bidirectional"))
      (node (ref "U13") (pin "6") (pinfunction "ICTRL-_6") (pintype "bidirectional"))
      (node (ref "U13") (pin "7") (pinfunction "ICTRL+_7") (pintype "bidirectional"))
      (node (ref "U14") (pin "4") (pinfunction "VCC_4") (pintype "input"))
    )
    (net (code "22") (name "/RADIO_XIN") (class "Default")
      (node (ref "C13") (pin "2") (pinfunction "P$2_2") (pintype "passive"))
      (node (ref "U2") (pin "17") (pinfunction "XIN_17") (pintype "input"))
    )
    (net (code "23") (name "/RTC_XI") (class "Default")
      (node (ref "C22") (pin "1") (pinfunction "P$1_1") (pintype "passive"))
      (node (ref "U9") (pin "$12") (pinfunction "RTC_XI_$12") (pintype "bidirectional"))
      (node (ref "Y1") (pin "1") (pinfunction "1_1") (pintype "passive"))
    )
    (net (code "24") (name "/RTC_XO") (class "Default")
      (node (ref "C23") (pin "1") (pinfunction "P$1_1") (pintype "passive"))
      (node (ref "U9") (pin "$13") (pinfunction "RTC_XO_$13") (pintype "bidirectional"))
      (node (ref "Y1") (pin "2") (pinfunction "2_2") (pintype "passive"))
    )
    (net (code "25") (name "/SAM_XOSC") (class "Default")
      (node (ref "C18") (pin "1") (pinfunction "P$1_1") (pintype "passive"))
      (node (ref "R10") (pin "1") (pinfunction "1_1") (pintype "passive"))
      (node (ref "R9") (pin "2") (pinfunction "2_2") (pintype "passive"))
      (node (ref "U1") (pin "15") (pinfunction "PA14_15") (pintype "bidirectional"))
    )
    (net (code "26") (name "/SCL") (class "Default")
      (node (ref "U$55") (pin "12") (pinfunction "SCL_12") (pintype "bidirectional"))
      (node (ref "U1") (pin "2") (pinfunction "PA01_2") (pintype "bidirectional"))
    )
    (net (code "27") (name "/SDA") (class "Default")
      (node (ref "U$55") (pin "19") (pinfunction "SDA_19") (pintype "bidirectional"))
      (node (ref "U1") (pin "1") (pinfunction "PA00_1") (pintype "bidirectional"))
    )
    (net (code "28") (name "/SE_ON_OFF") (class "Default")
      (node (ref "U1") (pin "16") (pinfunction "PA15_16") (pintype "bidirectional"))
      (node (ref "U9") (pin "$3") (pinfunction "ON_OFF_$3") (pintype "bidirectional"))
    )
    (net (code "29") (name "/SE_TCXO_CLK") (class "Default")
      (node (ref "U6") (pin "3") (pinfunction "OUT_3") (pintype "output"))
      (node (ref "U9") (pin "$21") (pinfunction "TCXO_CLK_$21") (pintype "bidirectional"))
    )
    (net (code "30") (name "/SI_GPIO0") (class "Default")
      (node (ref "U1") (pin "25") (pinfunction "PA27_25") (pintype "bidirectional"))
      (node (ref "U2") (pin "9") (pinfunction "GPIO0_9") (pintype "bidirectional"))
    )
    (net (code "31") (name "/SI_GPIO1") (class "Default")
      (node (ref "U1") (pin "24") (pinfunction "PA25_24") (pintype "bidirectional"))
      (node (ref "U2") (pin "10") (pinfunction "GPIO1_10") (pintype "bidirectional"))
    )
    (net (code "32") (name "/SI_MISO") (class "Default")
      (node (ref "U1") (pin "21") (pinfunction "PA22_21") (pintype "bidirectional"))
      (node (ref "U2") (pin "13") (pinfunction "SDO_13") (pintype "output"))
    )
    (net (code "33") (name "/SI_MOSI") (class "Default")
      (node (ref "U1") (pin "20") (pinfunction "PA19_20") (pintype "bidirectional"))
      (node (ref "U2") (pin "14") (pinfunction "SDI_14") (pintype "bidirectional"))
    )
    (net (code "34") (name "/SI_NIRQ") (class "Default")
      (node (ref "U1") (pin "23") (pinfunction "PA24_23") (pintype "bidirectional"))
      (node (ref "U2") (pin "11") (pinfunction "NIRQ_11") (pintype "output"))
    )
    (net (code "35") (name "/SI_NSEL") (class "Default")
      (node (ref "U1") (pin "19") (pinfunction "PA18_19") (pintype "bidirectional"))
      (node (ref "U2") (pin "15") (pinfunction "NSEL_15") (pintype "input"))
    )
    (net (code "36") (name "/SI_SCLK") (class "Default")
      (node (ref "U1") (pin "22") (pinfunction "PA23_22") (pintype "bidirectional"))
      (node (ref "U2") (pin "12") (pinfunction "SCLK_12") (pintype "input"))
    )
    (net (code "37") (name "/SI_SDN") (class "Default")
      (node (ref "U1") (pin "18") (pinfunction "PA17_18") (pintype "bidirectional"))
      (node (ref "U2") (pin "1") (pinfunction "SDN_1") (pintype "input"))
    )
    (net (code "38") (name "/SPV_VCTRL1") (class "Default")
      (node (ref "C32") (pin "1") (pinfunction "P$1_1") (pintype "passive"))
      (node (ref "R2") (pin "2") (pinfunction "2_2") (pintype "passive"))
      (node (ref "R3") (pin "1") (pinfunction "1_1") (pintype "passive"))
      (node (ref "U13") (pin "5") (pinfunction "VCTRL_5") (pintype "bidirectional"))
    )
    (net (code "39") (name "/SSC_DIS") (class "Default")
      (node (ref "R15") (pin "1") (pinfunction "1_1") (pintype "passive"))
      (node (ref "R16") (pin "2") (pinfunction "2_2") (pintype "passive"))
      (node (ref "U$55") (pin "5") (pinfunction "SSC_DIS_5") (pintype "bidirectional"))
    )
    (net (code "40") (name "/SUPERVISOR_VCC") (class "Default")
      (node (ref "C40") (pin "1") (pinfunction "P$1_1") (pintype "passive"))
      (node (ref "D3") (pin "C") (pinfunction "C_C") (pintype "passive"))
      (node (ref "D4") (pin "C") (pinfunction "C_C") (pintype "passive"))
      (node (ref "R11") (pin "2") (pinfunction "2_2") (pintype "passive"))
      (node (ref "R19") (pin "2") (pinfunction "2_2") (pintype "passive"))
      (node (ref "U11") (pin "1") (pinfunction "VDD_1") (pintype "bidirectional"))
      (node (ref "U12") (pin "5") (pinfunction "VCC_5") (pintype "power_in"))
    )
    (net (code "41") (name "/SWDCLK") (class "Default")
      (node (ref "U$74") (pin "$5") (pinfunction "5_$5") (pintype "passive"))
      (node (ref "U1") (pin "31") (pinfunction "PA30/SWCLK_31") (pintype "bidirectional"))
    )
    (net (code "42") (name "/SWDIO") (class "Default")
      (node (ref "U$74") (pin "$4") (pinfunction "4_$4") (pintype "passive"))
      (node (ref "U1") (pin "32") (pinfunction "PA31/SWDIO_32") (pintype "bidirectional"))
    )
    (net (code "43") (name "/TANK_EN") (class "Default")
      (node (ref "R19") (pin "1") (pinfunction "1_1") (pintype "passive"))
      (node (ref "U10") (pin "4") (pinfunction "EN_4") (pintype "bidirectional"))
      (node (ref "U11") (pin "6") (pinfunction "~{RESET}_6") (pintype "bidirectional"))
      (node (ref "U12") (pin "2") (pinfunction "A_2") (pintype "input"))
    )
    (net (code "44") (name "/TCXO_OUT") (class "Default")
      (node (ref "C13") (pin "1") (pinfunction "P$1_1") (pintype "passive"))
      (node (ref "C18") (pin "2") (pinfunction "P$2_2") (pintype "passive"))
      (node (ref "C26") (pin "1") (pinfunction "P$1_1") (pintype "passive"))
      (node (ref "U5") (pin "3") (pinfunction "OUT_3") (pintype "output"))
    )
    (net (code "45") (name "/TIMEPULSE") (class "Default")
      (node (ref "U1") (pin "6") (pinfunction "PA05_6") (pintype "bidirectional"))
      (node (ref "U3") (pin "4_TIMEPULSE") (pinfunction "4_TIMEPULSE_4_TIMEPULSE") (pintype "bidirectional"))
      (node (ref "U9") (pin "$4") (pinfunction "TM_$4") (pintype "bidirectional"))
    )
    (net (code "46") (name "/VBATT_SENSE") (class "Default")
      (node (ref "R7") (pin "2") (pinfunction "2_2") (pintype "passive"))
      (node (ref "R8") (pin "1") (pinfunction "1_1") (pintype "passive"))
      (node (ref "U1") (pin "3") (pinfunction "PA02_3") (pintype "bidirectional"))
    )
    (net (code "47") (name "/VSOLAR") (class "Default")
      (node (ref "C34") (pin "1") (pinfunction "P$1_1") (pintype "passive"))
      (node (ref "C35") (pin "1") (pinfunction "P$1_1") (pintype "passive"))
      (node (ref "R12") (pin "1") (pinfunction "1_1") (pintype "passive"))
      (node (ref "U$113") (pin "P$1") (pinfunction "1_P$1") (pintype "passive"))
      (node (ref "U1") (pin "5") (pinfunction "PA04_5") (pintype "bidirectional"))
      (node (ref "U13") (pin "8") (pinfunction "XSHUT_8") (pintype "bidirectional"))
    )
    (net (code "48") (name "/WDI") (class "Default")
      (node (ref "U1") (pin "27") (pinfunction "PA28_27") (pintype "bidirectional"))
      (node (ref "U7") (pin "4") (pinfunction "WDI_4") (pintype "bidirectional"))
    )
    (net (code "49") (name "/WDI~{RESET}") (class "Default")
      (node (ref "U7") (pin "1") (pinfunction "~{RESET}_1") (pintype "bidirectional"))
      (node (ref "U8") (pin "2") (pinfunction "B_2") (pintype "input"))
    )
    (net (code "50") (name "/~{RESET}") (class "Default")
      (node (ref "U1") (pin "26") (pinfunction "RESETN_26") (pintype "input"))
      (node (ref "U3") (pin "9_V_RESET") (pinfunction "9_V_RESET_9_V_RESET") (pintype "power_in"))
      (node (ref "U8") (pin "4") (pinfunction "Y_4") (pintype "output"))
      (node (ref "U9") (pin "$30") (pinfunction "NSRESET_$30") (pintype "bidirectional"))
    )
    (net (code "51") (name "1.8V") (class "Default")
      (node (ref "C10") (pin "1") (pinfunction "P$1_1") (pintype "passive"))
      (node (ref "C14") (pin "1") (pinfunction "P$1_1") (pintype "passive"))
      (node (ref "C15") (pin "1") (pinfunction "P$1_1") (pintype "passive"))
      (node (ref "C17") (pin "1") (pinfunction "P$1_1") (pintype "passive"))
      (node (ref "C19") (pin "1") (pinfunction "P$1_1") (pintype "passive"))
      (node (ref "C24") (pin "1") (pinfunction "P$1_1") (pintype "passive"))
      (node (ref "C25") (pin "1") (pinfunction "P$1_1") (pintype "passive"))
      (node (ref "C31") (pin "1") (pinfunction "1_1") (pintype "passive"))
      (node (ref "C41") (pin "1") (pinfunction "1_1") (pintype "passive"))
      (node (ref "C9") (pin "1") (pinfunction "P$1_1") (pintype "passive"))
      (node (ref "D2") (pin "A") (pinfunction "A_A") (pintype "passive"))
      (node (ref "FB1") (pin "2") (pinfunction "P$2_2") (pintype "passive"))
      (node (ref "FB2") (pin "2") (pinfunction "P$2_2") (pintype "passive"))
      (node (ref "FB3") (pin "2") (pinfunction "P$2_2") (pintype "passive"))
      (node (ref "L8") (pin "2") (pinfunction "2_2") (pintype "passive"))
      (node (ref "L9") (pin "2") (pinfunction "2_2") (pintype "passive"))
      (node (ref "R10") (pin "2") (pinfunction "2_2") (pintype "passive"))
      (node (ref "R15") (pin "2") (pinfunction "2_2") (pintype "passive"))
      (node (ref "R17") (pin "2") (pinfunction "2_2") (pintype "passive"))
      (node (ref "R4") (pin "2") (pinfunction "2_2") (pintype "passive"))
      (node (ref "U$19") (pin "8") (pinfunction "VDD_8") (pintype "power_in"))
      (node (ref "U$55") (pin "11") (pinfunction "VDDO_D_11") (pintype "bidirectional"))
      (node (ref "U$55") (pin "15") (pinfunction "VDDO_C_15") (pintype "bidirectional"))
      (node (ref "U$55") (pin "16") (pinfunction "VDDO_B_16") (pintype "bidirectional"))
      (node (ref "U$55") (pin "20") (pinfunction "VDDO_A_20") (pintype "bidirectional"))
      (node (ref "U$55") (pin "24") (pinfunction "VCC2_24") (pintype "bidirectional"))
      (node (ref "U$55") (pin "7") (pinfunction "VCC1_7") (pintype "bidirectional"))
      (node (ref "U$74") (pin "$3") (pinfunction "3_$3") (pintype "passive"))
      (node (ref "U1") (pin "30") (pinfunction "VDD_30") (pintype "power_in"))
      (node (ref "U1") (pin "9") (pinfunction "VDD_ANA_9") (pintype "power_in"))
      (node (ref "U10") (pin "3") (pinfunction "FB_3") (pintype "bidirectional"))
      (node (ref "U3") (pin "7_VCC_IO") (pinfunction "7_VCC_IO_7_VCC_IO") (pintype "power_in"))
      (node (ref "U3") (pin "8_VCC") (pinfunction "8_VCC_8_VCC") (pintype "power_in"))
      (node (ref "U4") (pin "3") (pinfunction "FB_3") (pintype "bidirectional"))
      (node (ref "U7") (pin "3") (pinfunction "~{MR}_3") (pintype "bidirectional"))
      (node (ref "U7") (pin "5") (pinfunction "VDD_5") (pintype "bidirectional"))
      (node (ref "U8") (pin "5") (pinfunction "VCC_5") (pintype "power_in"))
      (node (ref "U9") (pin "$8") (pinfunction "VKA_$8") (pintype "bidirectional"))
      (node (ref "U9") (pin "$9") (pinfunction "VDD_$9") (pintype "bidirectional"))
    )
    (net (code "52") (name "GND") (class "Default")
      (node (ref "C1") (pin "2") (pinfunction "P$2_2") (pintype "passive"))
      (node (ref "C10") (pin "2") (pinfunction "P$2_2") (pintype "passive"))
      (node (ref "C11") (pin "2") (pinfunction "P$2_2") (pintype "passive"))
      (node (ref "C12") (pin "2") (pinfunction "P$2_2") (pintype "passive"))
      (node (ref "C14") (pin "2") (pinfunction "P$2_2") (pintype "passive"))
      (node (ref "C15") (pin "2") (pinfunction "P$2_2") (pintype "passive"))
      (node (ref "C16") (pin "2") (pinfunction "P$2_2") (pintype "passive"))
      (node (ref "C17") (pin "2") (pinfunction "P$2_2") (pintype "passive"))
      (node (ref "C19") (pin "2") (pinfunction "P$2_2") (pintype "passive"))
      (node (ref "C2") (pin "2") (pinfunction "P$2_2") (pintype "passive"))
      (node (ref "C20") (pin "2") (pinfunction "P$2_2") (pintype "passive"))
      (node (ref "C21") (pin "2") (pinfunction "P$2_2") (pintype "passive"))
      (node (ref "C22") (pin "2") (pinfunction "P$2_2") (pintype "passive"))
      (node (ref "C23") (pin "2") (pinfunction "P$2_2") (pintype "passive"))
      (node (ref "C24") (pin "2") (pinfunction "P$2_2") (pintype "passive"))
      (node (ref "C25") (pin "2") (pinfunction "P$2_2") (pintype "passive"))
      (node (ref "C29") (pin "2") (pinfunction "P$2_2") (pintype "passive"))
      (node (ref "C3") (pin "2") (pinfunction "P$2_2") (pintype "passive"))
      (node (ref "C30") (pin "2") (pinfunction "P$2_2") (pintype "passive"))
      (node (ref "C31") (pin "2") (pinfunction "2_2") (pintype "passive"))
      (node (ref "C32") (pin "2") (pinfunction "P$2_2") (pintype "passive"))
      (node (ref "C33") (pin "1") (pinfunction "P$1_1") (pintype "passive"))
      (node (ref "C34") (pin "2") (pinfunction "P$2_2") (pintype "passive"))
      (node (ref "C35") (pin "2") (pinfunction "P$2_2") (pintype "passive"))
      (node (ref "C36") (pin "2") (pinfunction "P$2_2") (pintype "passive"))
      (node (ref "C37") (pin "2") (pinfunction "P$2_2") (pintype "passive"))
      (node (ref "C38") (pin "2") (pinfunction "P$2_2") (pintype "passive"))
      (node (ref "C39") (pin "2") (pinfunction "P$2_2") (pintype "passive"))
      (node (ref "C40") (pin "2") (pinfunction "P$2_2") (pintype "passive"))
      (node (ref "C41") (pin "2") (pinfunction "2_2") (pintype "passive"))
      (node (ref "C42") (pin "2") (pinfunction "P$2_2") (pintype "passive"))
      (node (ref "C5") (pin "2") (pinfunction "P$2_2") (pintype "passive"))
      (node (ref "C7") (pin "2") (pinfunction "P$2_2") (pintype "passive"))
      (node (ref "C8") (pin "2") (pinfunction "P$2_2") (pintype "passive"))
      (node (ref "C9") (pin "2") (pinfunction "P$2_2") (pintype "passive"))
      (node (ref "ESD1") (pin "1") (pinfunction "P$1_1") (pintype "passive"))
      (node (ref "ESD2") (pin "1") (pinfunction "P$1_1") (pintype "passive"))
      (node (ref "R1") (pin "1") (pinfunction "1_1") (pintype "passive"))
      (node (ref "R13") (pin "2") (pinfunction "2_2") (pintype "passive"))
      (node (ref "R14") (pin "2") (pinfunction "2_2") (pintype "passive"))
      (node (ref "R16") (pin "1") (pinfunction "1_1") (pintype "passive"))
      (node (ref "R2") (pin "1") (pinfunction "1_1") (pintype "passive"))
      (node (ref "R5") (pin "1") (pinfunction "1_1") (pintype "passive"))
      (node (ref "R6") (pin "1") (pinfunction "1_1") (pintype "passive"))
      (node (ref "R7") (pin "1") (pinfunction "1_1") (pintype "passive"))
      (node (ref "R9") (pin "1") (pinfunction "1_1") (pintype "passive"))
      (node (ref "U$19") (pin "4") (pinfunction "VSS_4") (pintype "power_in"))
      (node (ref "U$19") (pin "P$9") (pinfunction "GND_PAD_P$9") (pintype "power_in"))
      (node (ref "U$55") (pin "23") (pinfunction "GND_23") (pintype "bidirectional"))
      (node (ref "U$55") (pin "3") (pinfunction "I2C_LSB_3") (pintype "bidirectional"))
      (node (ref "U$55") (pin "6") (pinfunction "~{OE}_6") (pintype "bidirectional"))
      (node (ref "U$55") (pin "PAD") (pinfunction "GND_PAD_PAD") (pintype "bidirectional"))
      (node (ref "U$74") (pin "$1") (pinfunction "1_$1") (pintype "passive"))
      (node (ref "U1") (pin "10") (pinfunction "GND1_10") (pintype "power_in"))
      (node (ref "U1") (pin "28") (pinfunction "GND2_28") (pintype "power_in"))
      (node (ref "U1") (pin "33") (pinfunction "GND_33") (pintype "power_in"))
      (node (ref "U10") (pin "2") (pinfunction "MODE_2") (pintype "bidirectional"))
      (node (ref "U10") (pin "6") (pinfunction "GND_6") (pintype "bidirectional"))
      (node (ref "U10") (pin "PAD") (pinfunction "GND2_PAD") (pintype "bidirectional"))
      (node (ref "U11") (pin "5") (pinfunction "GND_5") (pintype "bidirectional"))
      (node (ref "U11") (pin "PAD") (pinfunction "GND2_PAD") (pintype "bidirectional"))
      (node (ref "U12") (pin "3") (pinfunction "GND_3") (pintype "passive"))
      (node (ref "U13") (pin "2") (pinfunction "GND_2") (pintype "power_in"))
      (node (ref "U14") (pin "2") (pinfunction "GND_2") (pintype "input"))
      (node (ref "U2") (pin "18") (pinfunction "GND2_18") (pintype "power_in"))
      (node (ref "U2") (pin "5") (pinfunction "NC/GND_5") (pintype "bidirectional"))
      (node (ref "U2") (pin "PAD") (pinfunction "GND_PAD") (pintype "power_in"))
      (node (ref "U3") (pin "10_GND") (pinfunction "10_GND_10_GND") (pintype "power_in"))
      (node (ref "U3") (pin "12_GND") (pinfunction "12_GND_12_GND") (pintype "power_in"))
      (node (ref "U3") (pin "1_GND") (pinfunction "1_GND_1_GND") (pintype "power_in"))
      (node (ref "U4") (pin "2") (pinfunction "MODE_2") (pintype "bidirectional"))
      (node (ref "U4") (pin "6") (pinfunction "GND_6") (pintype "bidirectional"))
      (node (ref "U4") (pin "PAD") (pinfunction "GND2_PAD") (pintype "bidirectional"))
      (node (ref "U44") (pin "1") (pinfunction "COM1_1") (pintype "bidirectional"))
      (node (ref "U44") (pin "4") (pinfunction "COM2_4") (pintype "bidirectional"))
      (node (ref "U44") (pin "5") (pinfunction "_COM2_5") (pintype "bidirectional"))
      (node (ref "U44") (pin "8") (pinfunction "COM1__8") (pintype "bidirectional"))
      (node (ref "U44") (pin "EPAD") (pinfunction "EPAD_EPAD") (pintype "bidirectional"))
      (node (ref "U5") (pin "2") (pinfunction "GND_2") (pintype "power_in"))
      (node (ref "U6") (pin "2") (pinfunction "GND_2") (pintype "power_in"))
      (node (ref "U7") (pin "2") (pinfunction "GND_2") (pintype "bidirectional"))
      (node (ref "U8") (pin "3") (pinfunction "GND_3") (pintype "passive"))
      (node (ref "U9") (pin "$1") (pinfunction "GND1_$1") (pintype "bidirectional"))
      (node (ref "U9") (pin "$18") (pinfunction "GND3_$18") (pintype "bidirectional"))
      (node (ref "U9") (pin "$20") (pinfunction "GND4_$20") (pintype "bidirectional"))
      (node (ref "U9") (pin "$23") (pinfunction "GND5_$23") (pintype "bidirectional"))
      (node (ref "U9") (pin "$24") (pinfunction "GND6_$24") (pintype "bidirectional"))
      (node (ref "U9") (pin "$25") (pinfunction "GND7_$25") (pintype "bidirectional"))
      (node (ref "U9") (pin "$26") (pinfunction "GND8_$26") (pintype "bidirectional"))
      (node (ref "U9") (pin "$28") (pinfunction "GND9_$28") (pintype "bidirectional"))
      (node (ref "U9") (pin "$29") (pinfunction "GND10_$29") (pintype "bidirectional"))
      (node (ref "U9") (pin "$5") (pinfunction "GND2_$5") (pintype "bidirectional"))
    )
    (net (code "53") (name "Net-(C2-P$1)") (class "Default")
      (node (ref "C2") (pin "1") (pinfunction "P$1_1") (pintype "passive"))
      (node (ref "L4") (pin "1") (pinfunction "1_1") (pintype "passive"))
      (node (ref "L5") (pin "2") (pinfunction "2_2") (pintype "passive"))
    )
    (net (code "54") (name "Net-(C3-P$1)") (class "Default")
      (node (ref "C3") (pin "1") (pinfunction "P$1_1") (pintype "passive"))
      (node (ref "C6") (pin "1") (pinfunction "P$1_1") (pintype "passive"))
      (node (ref "L3") (pin "1") (pinfunction "1_1") (pintype "passive"))
      (node (ref "L4") (pin "2") (pinfunction "2_2") (pintype "passive"))
      (node (ref "L7") (pin "1") (pinfunction "1_1") (pintype "passive"))
    )
    (net (code "55") (name "Net-(C4-P$1)") (class "Default")
      (node (ref "C4") (pin "1") (pinfunction "P$1_1") (pintype "passive"))
      (node (ref "L3") (pin "2") (pinfunction "2_2") (pintype "passive"))
    )
    (net (code "56") (name "Net-(C4-P$2)") (class "Default")
      (node (ref "C4") (pin "2") (pinfunction "P$2_2") (pintype "passive"))
      (node (ref "L2") (pin "1") (pinfunction "1_1") (pintype "passive"))
      (node (ref "U2") (pin "4") (pinfunction "TX_4") (pintype "output"))
    )
    (net (code "57") (name "Net-(C5-P$1)") (class "Default")
      (node (ref "C5") (pin "1") (pinfunction "P$1_1") (pintype "passive"))
      (node (ref "L6") (pin "1") (pinfunction "1_1") (pintype "passive"))
      (node (ref "L7") (pin "2") (pinfunction "2_2") (pintype "passive"))
      (node (ref "U2") (pin "3") (pinfunction "RXN_3") (pintype "input"))
    )
    (net (code "58") (name "Net-(C6-P$2)") (class "Default")
      (node (ref "C6") (pin "2") (pinfunction "P$2_2") (pintype "passive"))
      (node (ref "L6") (pin "2") (pinfunction "2_2") (pintype "passive"))
      (node (ref "U2") (pin "2") (pinfunction "RXP_2") (pintype "input"))
    )
    (net (code "59") (name "Net-(C11-P$1)") (class "Default")
      (node (ref "C11") (pin "1") (pinfunction "P$1_1") (pintype "passive"))
      (node (ref "C21") (pin "1") (pinfunction "P$1_1") (pintype "passive"))
      (node (ref "C7") (pin "1") (pinfunction "P$1_1") (pintype "passive"))
      (node (ref "C8") (pin "1") (pinfunction "P$1_1") (pintype "passive"))
      (node (ref "FB1") (pin "1") (pinfunction "P$1_1") (pintype "passive"))
      (node (ref "L2") (pin "2") (pinfunction "2_2") (pintype "passive"))
      (node (ref "U2") (pin "6") (pinfunction "VDD_6") (pintype "power_in"))
      (node (ref "U2") (pin "8") (pinfunction "VDD2_8") (pintype "power_in"))
    )
    (net (code "60") (name "Net-(C12-P$1)") (class "Default")
      (node (ref "C12") (pin "1") (pinfunction "P$1_1") (pintype "passive"))
      (node (ref "FB2") (pin "1") (pinfunction "P$1_1") (pintype "passive"))
      (node (ref "U5") (pin "4") (pinfunction "VCC_4") (pintype "power_in"))
    )
    (net (code "61") (name "Net-(C16-P$1)") (class "Default")
      (node (ref "C16") (pin "1") (pinfunction "P$1_1") (pintype "passive"))
      (node (ref "U1") (pin "29") (pinfunction "VDD_CORE_29") (pintype "power_in"))
    )
    (net (code "62") (name "Net-(C20-P$1)") (class "Default")
      (node (ref "C20") (pin "1") (pinfunction "P$1_1") (pintype "passive"))
      (node (ref "U6") (pin "4") (pinfunction "VCC_4") (pintype "power_in"))
      (node (ref "U9") (pin "$19") (pinfunction "VCC_TCXO_$19") (pintype "bidirectional"))
    )
    (net (code "63") (name "Net-(C26-P$2)") (class "Default")
      (node (ref "C26") (pin "2") (pinfunction "P$2_2") (pintype "passive"))
      (node (ref "U$55") (pin "1") (pinfunction "XA_1") (pintype "bidirectional"))
    )
    (net (code "64") (name "Net-(C33-P$2)") (class "Default")
      (node (ref "C33") (pin "2") (pinfunction "P$2_2") (pintype "passive"))
      (node (ref "R12") (pin "2") (pinfunction "2_2") (pintype "passive"))
      (node (ref "U13") (pin "1") (pinfunction "MPP-SET_1") (pintype "bidirectional"))
    )
    (net (code "65") (name "Net-(U$55-CLKIN)") (class "Default")
      (node (ref "R14") (pin "1") (pinfunction "1_1") (pintype "passive"))
      (node (ref "U$55") (pin "4") (pinfunction "CLKIN_4") (pintype "bidirectional"))
    )
    (net (code "66") (name "Net-(U$55-INTR)") (class "Default")
      (node (ref "R17") (pin "1") (pinfunction "1_1") (pintype "passive"))
      (node (ref "U$55") (pin "8") (pinfunction "INTR_8") (pintype "bidirectional"))
    )
    (net (code "67") (name "Net-(U$55-XB)") (class "Default")
      (node (ref "R13") (pin "1") (pinfunction "1_1") (pintype "passive"))
      (node (ref "U$55") (pin "2") (pinfunction "XB_2") (pintype "bidirectional"))
    )
    (net (code "68") (name "Net-(U$113-2)") (class "Default")
      (node (ref "U$113") (pin "P$2") (pinfunction "2_P$2") (pintype "passive"))
      (node (ref "U13") (pin "3") (pinfunction "LX_3") (pintype "bidirectional"))
    )
    (net (code "69") (name "Net-(U4-SW)") (class "Default")
      (node (ref "L8") (pin "1") (pinfunction "1_1") (pintype "passive"))
      (node (ref "U4") (pin "1") (pinfunction "SW_1") (pintype "bidirectional"))
    )
    (net (code "70") (name "Net-(U9-CTS_SPI)") (class "Default")
      (node (ref "R4") (pin "1") (pinfunction "1_1") (pintype "passive"))
      (node (ref "U9") (pin "$31") (pinfunction "CTS_SPI_$31") (pintype "bidirectional"))
    )
    (net (code "71") (name "Net-(U9-GPIO0)") (class "Default")
      (node (ref "R6") (pin "2") (pinfunction "2_2") (pintype "passive"))
      (node (ref "U9") (pin "$17") (pinfunction "GPIO0_$17") (pintype "bidirectional"))
    )
    (net (code "72") (name "Net-(U9-GPIO1)") (class "Default")
      (node (ref "R5") (pin "2") (pinfunction "2_2") (pintype "passive"))
      (node (ref "U9") (pin "$16") (pinfunction "GPIO1_$16") (pintype "bidirectional"))
    )
    (net (code "73") (name "Net-(U9-VBB_I)") (class "Default")
      (node (ref "U9") (pin "$6") (pinfunction "VBB_I_$6") (pintype "bidirectional"))
      (node (ref "U9") (pin "$7") (pinfunction "VREG_O_$7") (pintype "bidirectional"))
    )
    (net (code "74") (name "Net-(U10-SW)") (class "Default")
      (node (ref "L9") (pin "1") (pinfunction "1_1") (pintype "passive"))
      (node (ref "U10") (pin "1") (pinfunction "SW_1") (pintype "bidirectional"))
    )
    (net (code "75") (name "Net-(U14-PROG)") (class "Default")
      (node (ref "R18") (pin "2") (pinfunction "2_2") (pintype "passive"))
      (node (ref "U14") (pin "5") (pinfunction "PROG_5") (pintype "passive"))
    )
    (net (code "76") (name "unconnected-(C28-P$2-Pad2)") (class "Default")
      (node (ref "C28") (pin "2") (pinfunction "P$2_2") (pintype "passive"))
    )
    (net (code "77") (name "unconnected-(U$19-IO3{slash}RESETN-Pad7)") (class "Default")
      (node (ref "U$19") (pin "7") (pinfunction "IO3/RESETN_7") (pintype "output"))
    )
    (net (code "78") (name "unconnected-(U$55-CLK0-Pad22)") (class "Default")
      (node (ref "U$55") (pin "22") (pinfunction "CLK0_22") (pintype "bidirectional"))
    )
    (net (code "79") (name "unconnected-(U$55-CLK1-Pad21)") (class "Default")
      (node (ref "U$55") (pin "21") (pinfunction "CLK1_21") (pintype "bidirectional"))
    )
    (net (code "80") (name "unconnected-(U$55-CLK3-Pad17)") (class "Default")
      (node (ref "U$55") (pin "17") (pinfunction "CLK3_17") (pintype "bidirectional"))
    )
    (net (code "81") (name "unconnected-(U$55-CLK4-Pad14)") (class "Default")
      (node (ref "U$55") (pin "14") (pinfunction "CLK4_14") (pintype "bidirectional"))
    )
    (net (code "82") (name "unconnected-(U$55-CLK5-Pad13)") (class "Default")
      (node (ref "U$55") (pin "13") (pinfunction "CLK5_13") (pintype "bidirectional"))
    )
    (net (code "83") (name "unconnected-(U$55-CLK6-Pad10)") (class "Default")
      (node (ref "U$55") (pin "10") (pinfunction "CLK6_10") (pintype "bidirectional"))
    )
    (net (code "84") (name "unconnected-(U$55-CLK7-Pad9)") (class "Default")
      (node (ref "U$55") (pin "9") (pinfunction "CLK7_9") (pintype "bidirectional"))
    )
    (net (code "85") (name "unconnected-(U2-GPIO2-Pad19)") (class "Default")
      (node (ref "U2") (pin "19") (pinfunction "GPIO2_19") (pintype "bidirectional"))
    )
    (net (code "86") (name "unconnected-(U2-GPIO3-Pad20)") (class "Default")
      (node (ref "U2") (pin "20") (pinfunction "GPIO3_20") (pintype "bidirectional"))
    )
    (net (code "87") (name "unconnected-(U2-TXRAMP-Pad7)") (class "Default")
      (node (ref "U2") (pin "7") (pinfunction "TXRAMP_7") (pintype "bidirectional"))
    )
    (net (code "88") (name "unconnected-(U2-XOUT-Pad16)") (class "Default")
      (node (ref "U2") (pin "16") (pinfunction "XOUT_16") (pintype "output"))
    )
    (net (code "89") (name "unconnected-(U3-Pad5_EXTINT0)") (class "Default")
      (node (ref "U3") (pin "5_EXTINT0") (pinfunction "5_EXTINT0_5_EXTINT0") (pintype "bidirectional"))
    )
    (net (code "90") (name "unconnected-(U3-Pad6_V_BCKP)") (class "Default")
      (node (ref "U3") (pin "6_V_BCKP") (pinfunction "6_V_BCKP_6_V_BCKP") (pintype "bidirectional"))
    )
    (net (code "91") (name "unconnected-(U3-Pad13_ANTON)") (class "Default")
      (node (ref "U3") (pin "13_ANTON") (pinfunction "13_ANTON_13_ANTON") (pintype "bidirectional"))
    )
    (net (code "92") (name "unconnected-(U3-Pad14_VCC_RF)") (class "Default")
      (node (ref "U3") (pin "14_VCC_RF") (pinfunction "14_VCC_RF_14_VCC_RF") (pintype "bidirectional"))
    )
    (net (code "93") (name "unconnected-(U3-Pad15_RESERVED)") (class "Default")
      (node (ref "U3") (pin "15_RESERVED") (pinfunction "15_RESERVED_15_RESERVED") (pintype "bidirectional"))
    )
    (net (code "94") (name "unconnected-(U3-Pad16_SDA2)") (class "Default")
      (node (ref "U3") (pin "16_SDA2") (pinfunction "16_SDA2_16_SDA2") (pintype "bidirectional"))
    )
    (net (code "95") (name "unconnected-(U3-Pad17_SCL2)") (class "Default")
      (node (ref "U3") (pin "17_SCL2") (pinfunction "17_SCL2_17_SCL2") (pintype "bidirectional"))
    )
    (net (code "96") (name "unconnected-(U3-Pad18_RESERVED)") (class "Default")
      (node (ref "U3") (pin "18_RESERVED") (pinfunction "18_RESERVED_18_RESERVED") (pintype "bidirectional"))
    )
    (net (code "97") (name "unconnected-(U5-NC-Pad1)") (class "Default")
      (node (ref "U5") (pin "1") (pinfunction "NC_1") (pintype "no_connect"))
    )
    (net (code "98") (name "unconnected-(U6-NC-Pad1)") (class "Default")
      (node (ref "U6") (pin "1") (pinfunction "NC_1") (pintype "no_connect"))
    )
    (net (code "99") (name "unconnected-(U9-GPIO2-Pad$15)") (class "Default")
      (node (ref "U9") (pin "$15") (pinfunction "GPIO2_$15") (pintype "bidirectional"))
    )
    (net (code "100") (name "unconnected-(U9-GPIO3-Pad$11)") (class "Default")
      (node (ref "U9") (pin "$11") (pinfunction "GPIO3_$11") (pintype "bidirectional"))
    )
    (net (code "101") (name "unconnected-(U9-GPIO4-Pad$14)") (class "Default")
      (node (ref "U9") (pin "$14") (pinfunction "GPIO4_$14") (pintype "bidirectional"))
    )
    (net (code "102") (name "unconnected-(U9-GPIO8-Pad$10)") (class "Default")
      (node (ref "U9") (pin "$10") (pinfunction "GPIO8_$10") (pintype "bidirectional"))
    )
    (net (code "103") (name "unconnected-(U9-RTS_SPI-Pad$32)") (class "Default")
      (node (ref "U9") (pin "$32") (pinfunction "RTS_SPI_$32") (pintype "bidirectional"))
    )
    (net (code "104") (name "unconnected-(U9-SYSTEM_ON-Pad$2)") (class "Default")
      (node (ref "U9") (pin "$2") (pinfunction "SYSTEM_ON_$2") (pintype "bidirectional"))
    )
    (net (code "105") (name "unconnected-(U9-XTAL_CLK-Pad$22)") (class "Default")
      (node (ref "U9") (pin "$22") (pinfunction "XTAL_CLK_$22") (pintype "bidirectional"))
    )
    (net (code "106") (name "unconnected-(U11-~{MR}-Pad4)") (class "Default")
      (node (ref "U11") (pin "4") (pinfunction "~{MR}_4") (pintype "bidirectional"))
    )
    (net (code "107") (name "unconnected-(U12-N.C.-Pad1)") (class "Default")
      (node (ref "U12") (pin "1") (pinfunction "N.C._1") (pintype "no_connect"))
    )
    (net (code "108") (name "unconnected-(U44-NC-Pad2)") (class "Default")
      (node (ref "U44") (pin "2") (pinfunction "NC_2") (pintype "bidirectional"))
    )
  )
)
